# Switches.net
KiCad netlist of a schematic drawn in Altium Designer
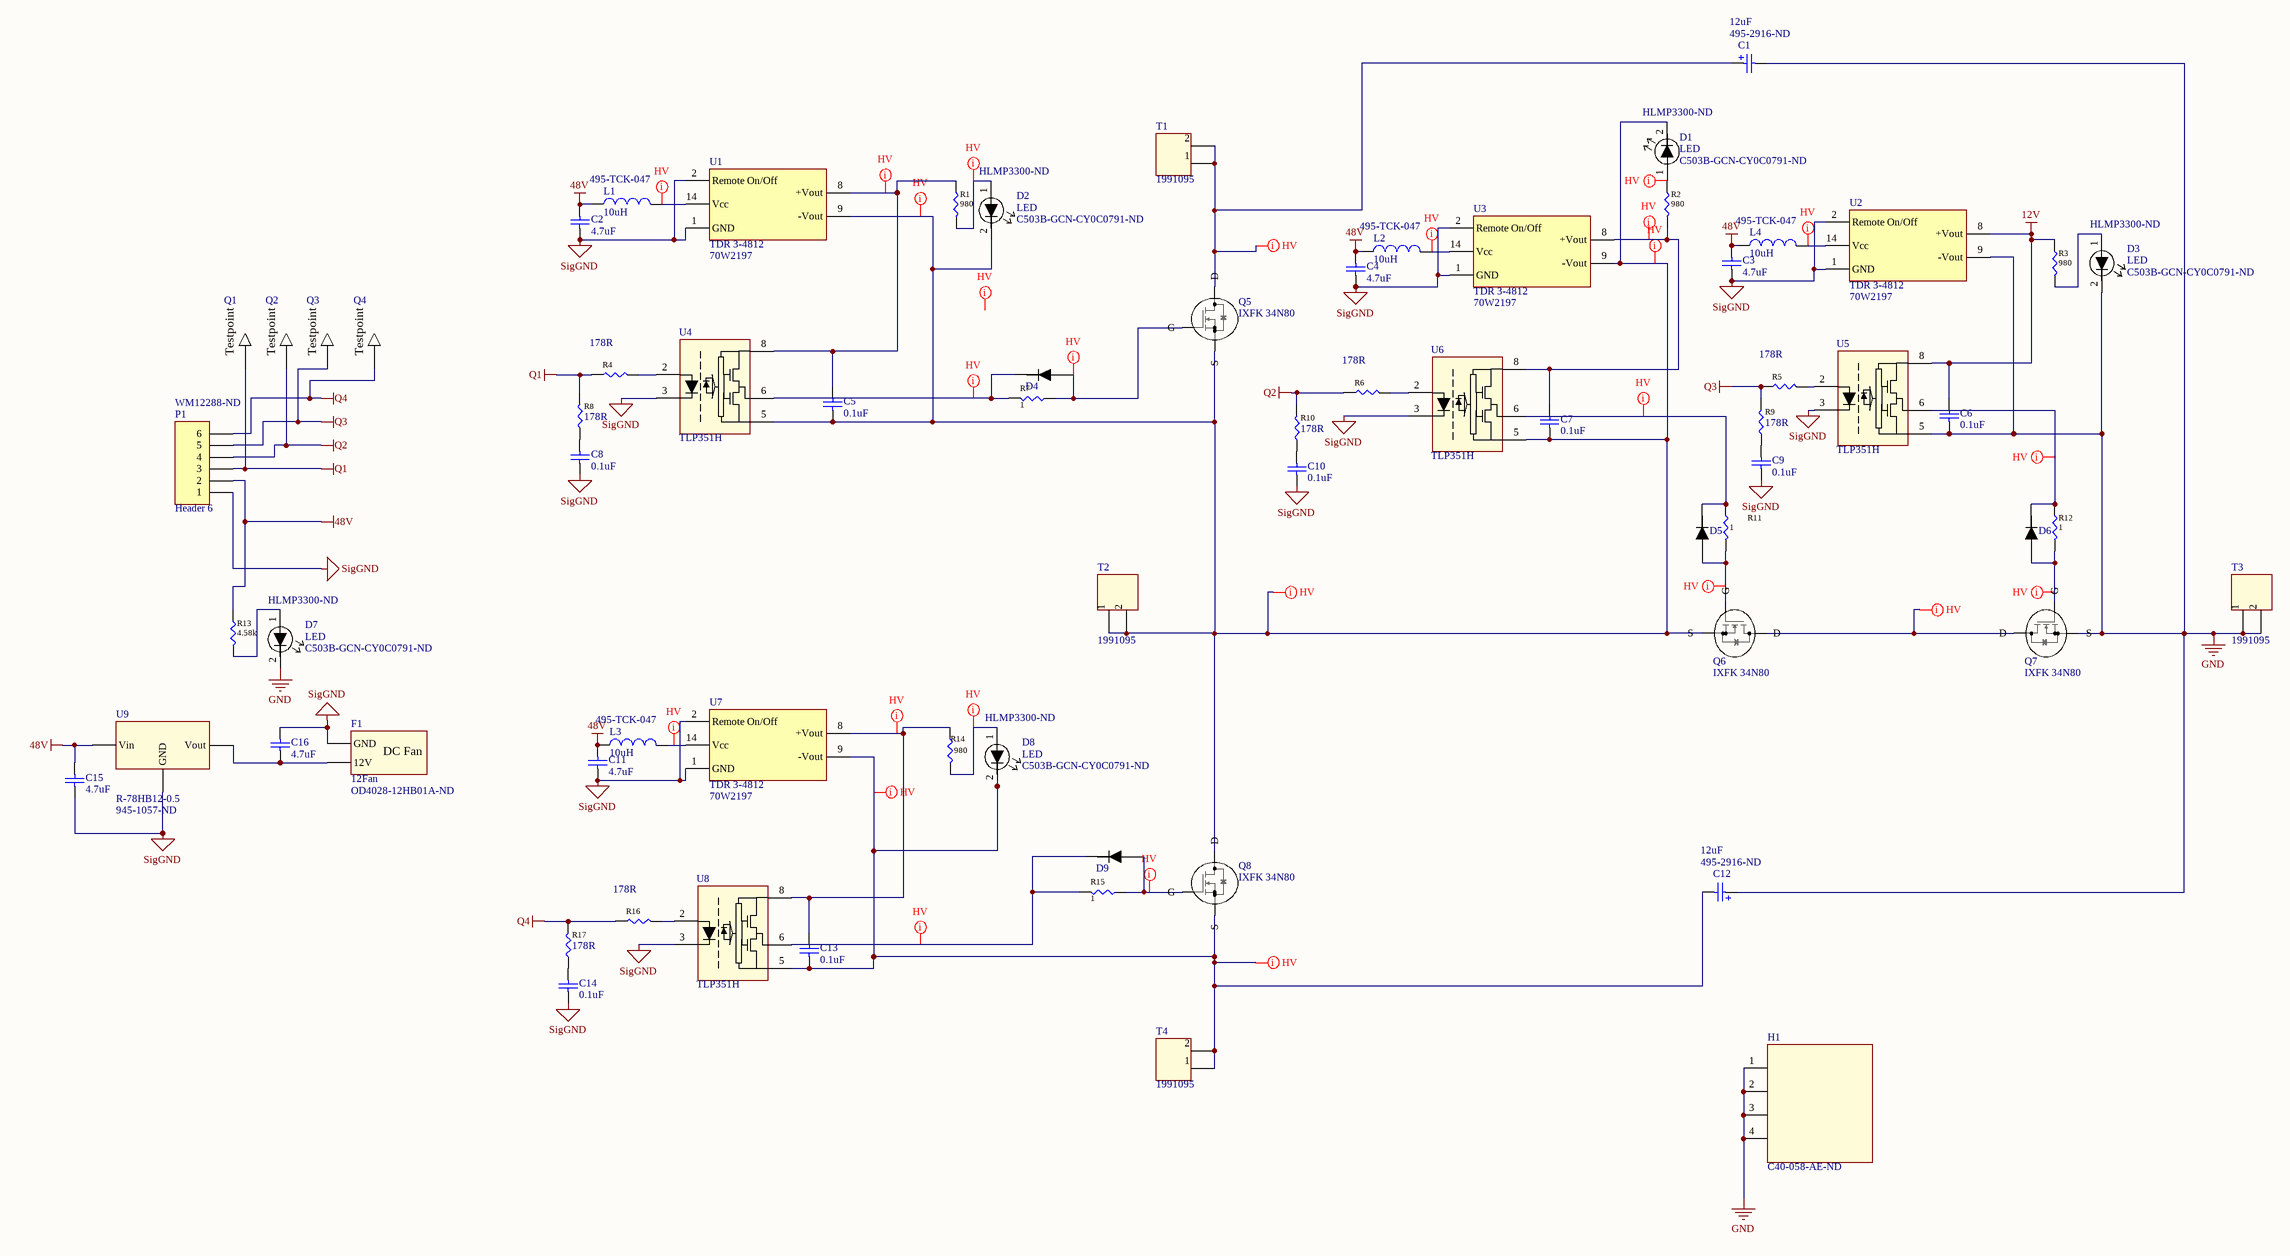
[diagram p0: Switches.SchDoc]

(export (version "E")
  (design (tool "Eeschema 10.0.6"))
  (components
    (comp (ref "C1")
      (value "Cap Pol1")
      (footprint "B32674D3126K000")
      (description "Polarized Capacitor (Radial)")
      (fields
        (field (name "SUPPLIER PART NUMBER 1") "495-2916-ND")
        (field (name "MANUFACTURER") "TDK EPCOS")
        (field (name "MANUFACTURER PART NUMBER") "B32674D3126K000")
        (field (name "CAPACITANCE") "12uF")
        (field (name "PUBLISHER") "Altium Limited")
      )
      (libsource (lib "T-Type Converter") (part "Cap Pol1"))
    )
    (comp (ref "C2")
      (value "4.7uF")
      (footprint "C4532")
      (description "Capacitor")
      (fields
        (field (name "MANUFACTURER") "TDK")
        (field (name "MANUFACTURER PART NUMBER") "CGA8N3X7S2A475K230KB")
        (field (name "PUBLISHER") "Altium Limited")
      )
      (libsource (lib "T-Type Converter") (part "Cap"))
    )
    (comp (ref "C3")
      (value "4.7uF")
      (footprint "C4532")
      (description "Capacitor")
      (fields
        (field (name "MANUFACTURER") "TDK")
        (field (name "MANUFACTURER PART NUMBER") "CGA8N3X7S2A475K230KB")
        (field (name "PUBLISHER") "Altium Limited")
      )
      (libsource (lib "T-Type Converter") (part "Cap"))
    )
    (comp (ref "C4")
      (value "4.7uF")
      (footprint "C4532")
      (description "Capacitor")
      (fields
        (field (name "MANUFACTURER") "TDK")
        (field (name "MANUFACTURER PART NUMBER") "CGA8N3X7S2A475K230KB")
        (field (name "PUBLISHER") "Altium Limited")
      )
      (libsource (lib "T-Type Converter") (part "Cap"))
    )
    (comp (ref "C5")
      (value "0.1uF")
      (footprint "R_1206")
      (description "Capacitor")
      (fields (field (name "Comment") "Cap") (field (name "PUBLISHER") "Altium Limited"))
      (libsource (lib "T-Type Converter") (part "Cap"))
    )
    (comp (ref "C6")
      (value "0.1uF")
      (footprint "R_1206")
      (description "Capacitor")
      (fields (field (name "Comment") "Cap") (field (name "PUBLISHER") "Altium Limited"))
      (libsource (lib "T-Type Converter") (part "Cap"))
    )
    (comp (ref "C7")
      (value "0.1uF")
      (footprint "R_1206")
      (description "Capacitor")
      (fields (field (name "Comment") "Cap") (field (name "PUBLISHER") "Altium Limited"))
      (libsource (lib "T-Type Converter") (part "Cap"))
    )
    (comp (ref "C8")
      (value "0.1uF")
      (footprint "Capacitor 0805 - duplicate")
      (description "Capacitor")
      (fields (field (name "Comment") "Cap") (field (name "PUBLISHER") "Altium Limited"))
      (libsource (lib "T-Type Converter") (part "Cap"))
    )
    (comp (ref "C9")
      (value "0.1uF")
      (footprint "Capacitor 0805 - duplicate")
      (description "Capacitor")
      (fields (field (name "Comment") "Cap") (field (name "PUBLISHER") "Altium Limited"))
      (libsource (lib "T-Type Converter") (part "Cap"))
    )
    (comp (ref "C10")
      (value "0.1uF")
      (footprint "Capacitor 0805 - duplicate")
      (description "Capacitor")
      (fields (field (name "Comment") "Cap") (field (name "PUBLISHER") "Altium Limited"))
      (libsource (lib "T-Type Converter") (part "Cap"))
    )
    (comp (ref "C11")
      (value "4.7uF")
      (footprint "C4532")
      (description "Capacitor")
      (fields
        (field (name "MANUFACTURER") "TDK")
        (field (name "MANUFACTURER PART NUMBER") "CGA8N3X7S2A475K230KB")
        (field (name "PUBLISHER") "Altium Limited")
      )
      (libsource (lib "T-Type Converter") (part "Cap"))
    )
    (comp (ref "C12")
      (value "Cap Pol1")
      (footprint "B32674D3126K000")
      (description "Polarized Capacitor (Radial)")
      (fields
        (field (name "SUPPLIER PART NUMBER 1") "495-2916-ND")
        (field (name "MANUFACTURER") "TDK EPCOS")
        (field (name "MANUFACTURER PART NUMBER") "B32674D3126K000")
        (field (name "CAPACITANCE") "12uF")
        (field (name "PUBLISHER") "Altium Limited")
      )
      (libsource (lib "T-Type Converter") (part "Cap Pol1"))
    )
    (comp (ref "C13")
      (value "0.1uF")
      (footprint "R_1206")
      (description "Capacitor")
      (fields (field (name "Comment") "Cap") (field (name "PUBLISHER") "Altium Limited"))
      (libsource (lib "T-Type Converter") (part "Cap"))
    )
    (comp (ref "C14")
      (value "0.1uF")
      (footprint "Capacitor 0805 - duplicate")
      (description "Capacitor")
      (fields (field (name "Comment") "Cap") (field (name "PUBLISHER") "Altium Limited"))
      (libsource (lib "T-Type Converter") (part "Cap"))
    )
    (comp (ref "C15")
      (value "4.7uF")
      (footprint "C4532")
      (description "Capacitor")
      (fields
        (field (name "MANUFACTURER") "TDK")
        (field (name "MANUFACTURER PART NUMBER") "CGA8N3X7S2A475K230KB")
        (field (name "PUBLISHER") "Altium Limited")
      )
      (libsource (lib "T-Type Converter") (part "Cap"))
    )
    (comp (ref "C16")
      (value "4.7uF")
      (footprint "C4532")
      (description "Capacitor")
      (fields
        (field (name "MANUFACTURER") "TDK")
        (field (name "MANUFACTURER PART NUMBER") "CGA8N3X7S2A475K230KB")
        (field (name "PUBLISHER") "Altium Limited")
      )
      (libsource (lib "T-Type Converter") (part "Cap"))
    )
    (comp (ref "D1")
      (value "LED")
      (footprint "LED")
      (fields
        (field (name "MANUFACTURER") "Cree")
        (field (name "MANUFACTURER PART NUMBER") "C503B-GCN-CY0C0791")
        (field (name "SUPPLIER PART NUMBER 1") "C503B-GCN-CY0C0791-ND")
        (field (name "SUPPLIER PART NUMBER 2") "HLMP3300-ND")
      )
      (libsource (lib "T-Type Converter") (part "LED"))
    )
    (comp (ref "D2")
      (value "LED")
      (footprint "LED")
      (fields
        (field (name "MANUFACTURER") "Cree")
        (field (name "MANUFACTURER PART NUMBER") "C503B-GCN-CY0C0791")
        (field (name "SUPPLIER PART NUMBER 1") "C503B-GCN-CY0C0791-ND")
        (field (name "SUPPLIER PART NUMBER 2") "HLMP3300-ND")
      )
      (libsource (lib "T-Type Converter") (part "LED"))
    )
    (comp (ref "D3")
      (value "LED")
      (footprint "LED")
      (fields
        (field (name "MANUFACTURER") "Cree")
        (field (name "MANUFACTURER PART NUMBER") "C503B-GCN-CY0C0791")
        (field (name "SUPPLIER PART NUMBER 1") "C503B-GCN-CY0C0791-ND")
        (field (name "SUPPLIER PART NUMBER 2") "HLMP3300-ND")
      )
      (libsource (lib "T-Type Converter") (part "LED"))
    )
    (comp (ref "D4")
      (value "1N4148")
      (footprint "DO-35_02")
      (description "Diode")
      (fields (field (name "MANUFACTURER") "Fairchild Semiconductor"))
      (libsource (lib "T-Type Converter") (part "1N4148"))
    )
    (comp (ref "D5")
      (value "1N4148")
      (footprint "DO-35_02")
      (description "Diode")
      (fields (field (name "MANUFACTURER") "Fairchild Semiconductor"))
      (libsource (lib "T-Type Converter") (part "1N4148"))
    )
    (comp (ref "D6")
      (value "1N4148")
      (footprint "DO-35_02")
      (description "Diode")
      (fields (field (name "MANUFACTURER") "Fairchild Semiconductor"))
      (libsource (lib "T-Type Converter") (part "1N4148"))
    )
    (comp (ref "D7")
      (value "LED")
      (footprint "LED")
      (fields
        (field (name "MANUFACTURER") "Cree")
        (field (name "MANUFACTURER PART NUMBER") "C503B-GCN-CY0C0791")
        (field (name "SUPPLIER PART NUMBER 1") "C503B-GCN-CY0C0791-ND")
        (field (name "SUPPLIER PART NUMBER 2") "HLMP3300-ND")
      )
      (libsource (lib "T-Type Converter") (part "LED"))
    )
    (comp (ref "D8")
      (value "LED")
      (footprint "LED")
      (fields
        (field (name "MANUFACTURER") "Cree")
        (field (name "MANUFACTURER PART NUMBER") "C503B-GCN-CY0C0791")
        (field (name "SUPPLIER PART NUMBER 1") "C503B-GCN-CY0C0791-ND")
        (field (name "SUPPLIER PART NUMBER 2") "HLMP3300-ND")
      )
      (libsource (lib "T-Type Converter") (part "LED"))
    )
    (comp (ref "D9")
      (value "1N4148")
      (footprint "DO-35_02")
      (description "Diode")
      (fields (field (name "MANUFACTURER") "Fairchild Semiconductor"))
      (libsource (lib "T-Type Converter") (part "1N4148"))
    )
    (comp (ref "F1")
      (value "12Fan")
      (footprint "12V Fan")
      (fields
        (field (name "MANUFACTURER") "Knight Electronics Orion")
        (field (name "MANUFACTURER PART NUMBER") "OD4028-12HB01A")
        (field (name "SUPPLIER PART NUMBER 1") "OD4028-12HB01A-ND")
      )
      (libsource (lib "T-Type Converter") (part "12Fan"))
    )
    (comp (ref "H1")
      (value "Heatsink")
      (footprint "Dual C40")
      (description "Dual C-40 Heatsink")
      (fields
        (field (name "MANUFACTURER") "Ohmite")
        (field (name "MANUFACTURER PART NUMBER") "C40-058-AE")
        (field (name "SUPPLIER PART NUMBER 1") "C40-058-AE-ND")
      )
      (libsource (lib "T-Type Converter") (part "C-40 Heatsink"))
    )
    (comp (ref "L1")
      (value "10uH")
      (footprint "TCK-047")
      (description "Inductor")
      (fields
        (field (name "SUPPLIER PART NUMBER 1") "495-TCK-047")
        (field (name "MANUFACTURER") "Traco Power")
        (field (name "MANUFACTURER PART NUMBER") "TCK-047")
        (field (name "PUBLISHER") "Altium Limited")
      )
      (libsource (lib "Miscellaneous Devices") (part "Inductor"))
    )
    (comp (ref "L2")
      (value "10uH")
      (footprint "TCK-047")
      (description "Inductor")
      (fields
        (field (name "SUPPLIER PART NUMBER 1") "495-TCK-047")
        (field (name "MANUFACTURER") "Traco Power")
        (field (name "MANUFACTURER PART NUMBER") "TCK-047")
        (field (name "PUBLISHER") "Altium Limited")
      )
      (libsource (lib "Miscellaneous Devices") (part "Inductor"))
    )
    (comp (ref "L3")
      (value "10uH")
      (footprint "TCK-047")
      (description "Inductor")
      (fields
        (field (name "SUPPLIER PART NUMBER 1") "495-TCK-047")
        (field (name "MANUFACTURER") "Traco Power")
        (field (name "MANUFACTURER PART NUMBER") "TCK-047")
        (field (name "PUBLISHER") "Altium Limited")
      )
      (libsource (lib "Miscellaneous Devices") (part "Inductor"))
    )
    (comp (ref "L4")
      (value "10uH")
      (footprint "TCK-047")
      (description "Inductor")
      (fields
        (field (name "SUPPLIER PART NUMBER 1") "495-TCK-047")
        (field (name "MANUFACTURER") "Traco Power")
        (field (name "MANUFACTURER PART NUMBER") "TCK-047")
        (field (name "PUBLISHER") "Altium Limited")
      )
      (libsource (lib "Miscellaneous Devices") (part "Inductor"))
    )
    (comp (ref "P1")
      (value "Header 6")
      (footprint "3.00mm Male Header")
      (description "Header, 6-Pin")
      (fields
        (field (name "SUPPLIER PART NUMBER 1") "WM12288-ND")
        (field (name "MANUFACTURER") "Molex")
        (field (name "MANUFACTURER PART NUMBER") "0559320610")
        (field (name "PUBLISHER") "Altium Limited")
      )
      (libsource (lib "Miscellaneous Connectors") (part "Header 6"))
    )
    (comp (ref "Q1")
      (value "Testpoint")
      (footprint "Testpoint")
      (libsource (lib "T-Type Converter") (part "Testpoint"))
    )
    (comp (ref "Q2")
      (value "Testpoint")
      (footprint "Testpoint")
      (libsource (lib "T-Type Converter") (part "Testpoint"))
    )
    (comp (ref "Q3")
      (value "Testpoint")
      (footprint "Testpoint")
      (libsource (lib "T-Type Converter") (part "Testpoint"))
    )
    (comp (ref "Q4")
      (value "Testpoint")
      (footprint "Testpoint")
      (libsource (lib "T-Type Converter") (part "Testpoint"))
    )
    (comp (ref "Q5")
      (value "IXFK 34N80")
      (footprint "TO-247")
      (description "MOSFET 34A")
      (fields (field (name "MANUFACTURER") "IXYS") (field (name "MANUFACTURER PART NUMBER") "IXFK34N80"))
      (libsource (lib "") (part "IXFK 34N80_2"))
    )
    (comp (ref "Q6")
      (value "IXFK 34N80")
      (footprint "TO-247")
      (description "MOSFET 34A")
      (fields (field (name "MANUFACTURER") "IXYS") (field (name "MANUFACTURER PART NUMBER") "IXFK34N80"))
      (libsource (lib "T-Type Converter") (part "IXFK 34N80"))
    )
    (comp (ref "Q7")
      (value "IXFK 34N80")
      (footprint "TO-247")
      (description "MOSFET 34A")
      (fields (field (name "MANUFACTURER") "IXYS") (field (name "MANUFACTURER PART NUMBER") "IXFK34N80"))
      (libsource (lib "") (part "IXFK 34N80_1"))
    )
    (comp (ref "Q8")
      (value "IXFK 34N80")
      (footprint "TO-247")
      (description "MOSFET 34A")
      (fields (field (name "MANUFACTURER") "IXYS") (field (name "MANUFACTURER PART NUMBER") "IXFK34N80"))
      (libsource (lib "") (part "IXFK 34N80_2"))
    )
    (comp (ref "R1")
      (value "980")
      (footprint "R_1206")
      (description "RES SMD 1% 1/4W 1206")
      (fields
        (field (name "MANUFACTURER") "Panasonic Electronic Components")
        (field (name "MANUFACTURER PART NUMBER") "ERJ-8ENF9101V")
      )
      (libsource (lib "T-Type Converter") (part "RES_SMD1"))
    )
    (comp (ref "R2")
      (value "980")
      (footprint "R_1206")
      (description "RES SMD 1% 1/4W 1206")
      (fields
        (field (name "MANUFACTURER") "Panasonic Electronic Components")
        (field (name "MANUFACTURER PART NUMBER") "ERJ-8ENF9101V")
      )
      (libsource (lib "T-Type Converter") (part "RES_SMD1"))
    )
    (comp (ref "R3")
      (value "980")
      (footprint "R_1206")
      (description "RES SMD 1% 1/4W 1206")
      (fields
        (field (name "MANUFACTURER") "Panasonic Electronic Components")
        (field (name "MANUFACTURER PART NUMBER") "ERJ-8ENF9101V")
      )
      (libsource (lib "T-Type Converter") (part "RES_SMD1"))
    )
    (comp (ref "R4")
      (value "~")
      (footprint "R_1206")
      (description "RES SMD 1% 1/4W 1206")
      (fields
        (field (name "MANUFACTURER") "Panasonic ECG")
        (field (name "MANUFACTURER PART NUMBER") "ERJ-8ENF1780V")
        (field (name "RESISTANCE") "178R")
      )
      (libsource (lib "T-Type Converter") (part "RES_SMD1"))
    )
    (comp (ref "R5")
      (value "~")
      (footprint "R_1206")
      (description "RES SMD 1% 1/4W 1206")
      (fields
        (field (name "MANUFACTURER") "Panasonic ECG")
        (field (name "MANUFACTURER PART NUMBER") "ERJ-8ENF1780V")
        (field (name "RESISTANCE") "178R")
      )
      (libsource (lib "T-Type Converter") (part "RES_SMD1"))
    )
    (comp (ref "R6")
      (value "~")
      (footprint "R_1206")
      (description "RES SMD 1% 1/4W 1206")
      (fields
        (field (name "MANUFACTURER") "Panasonic ECG")
        (field (name "MANUFACTURER PART NUMBER") "ERJ-8ENF1780V")
        (field (name "RESISTANCE") "178R")
      )
      (libsource (lib "T-Type Converter") (part "RES_SMD1"))
    )
    (comp (ref "R7")
      (value "1")
      (footprint "R_1206")
      (description "RES SMD 1% 1/4W 1206")
      (fields
        (field (name "MANUFACTURER") "Panasonic Electronic Components")
        (field (name "MANUFACTURER PART NUMBER") "ERJ-8ENF9101V")
      )
      (libsource (lib "T-Type Converter") (part "RES_SMD1"))
    )
    (comp (ref "R8")
      (value "~")
      (footprint "R_1206")
      (description "RES SMD 1% 1/4W 1206")
      (fields
        (field (name "MANUFACTURER") "Panasonic ECG")
        (field (name "MANUFACTURER PART NUMBER") "ERJ-8ENF1780V")
        (field (name "RESISTANCE") "178R")
      )
      (libsource (lib "T-Type Converter") (part "RES_SMD1"))
    )
    (comp (ref "R9")
      (value "~")
      (footprint "R_1206")
      (description "RES SMD 1% 1/4W 1206")
      (fields
        (field (name "MANUFACTURER") "Panasonic ECG")
        (field (name "MANUFACTURER PART NUMBER") "ERJ-8ENF1780V")
        (field (name "RESISTANCE") "178R")
      )
      (libsource (lib "T-Type Converter") (part "RES_SMD1"))
    )
    (comp (ref "R10")
      (value "~")
      (footprint "R_1206")
      (description "RES SMD 1% 1/4W 1206")
      (fields
        (field (name "MANUFACTURER") "Panasonic ECG")
        (field (name "MANUFACTURER PART NUMBER") "ERJ-8ENF1780V")
        (field (name "RESISTANCE") "178R")
      )
      (libsource (lib "T-Type Converter") (part "RES_SMD1"))
    )
    (comp (ref "R11")
      (value "1")
      (footprint "R_1206")
      (description "RES SMD 1% 1/4W 1206")
      (fields
        (field (name "MANUFACTURER") "Panasonic Electronic Components")
        (field (name "MANUFACTURER PART NUMBER") "ERJ-8ENF9101V")
      )
      (libsource (lib "T-Type Converter") (part "RES_SMD1"))
    )
    (comp (ref "R12")
      (value "1")
      (footprint "R_1206")
      (description "RES SMD 1% 1/4W 1206")
      (fields
        (field (name "MANUFACTURER") "Panasonic Electronic Components")
        (field (name "MANUFACTURER PART NUMBER") "ERJ-8ENF9101V")
      )
      (libsource (lib "T-Type Converter") (part "RES_SMD1"))
    )
    (comp (ref "R13")
      (value "4.58k")
      (footprint "R_1206")
      (description "RES SMD 1% 1/4W 1206")
      (fields
        (field (name "MANUFACTURER") "Panasonic Electronic Components")
        (field (name "MANUFACTURER PART NUMBER") "ERJ-8ENF9101V")
      )
      (libsource (lib "T-Type Converter") (part "RES_SMD1"))
    )
    (comp (ref "R14")
      (value "980")
      (footprint "R_1206")
      (description "RES SMD 1% 1/4W 1206")
      (fields
        (field (name "MANUFACTURER") "Panasonic Electronic Components")
        (field (name "MANUFACTURER PART NUMBER") "ERJ-8ENF9101V")
      )
      (libsource (lib "T-Type Converter") (part "RES_SMD1"))
    )
    (comp (ref "R15")
      (value "1")
      (footprint "R_1206")
      (description "RES SMD 1% 1/4W 1206")
      (fields
        (field (name "MANUFACTURER") "Panasonic Electronic Components")
        (field (name "MANUFACTURER PART NUMBER") "ERJ-8ENF9101V")
      )
      (libsource (lib "T-Type Converter") (part "RES_SMD1"))
    )
    (comp (ref "R16")
      (value "~")
      (footprint "R_1206")
      (description "RES SMD 1% 1/4W 1206")
      (fields
        (field (name "MANUFACTURER") "Panasonic ECG")
        (field (name "MANUFACTURER PART NUMBER") "ERJ-8ENF1780V")
        (field (name "RESISTANCE") "178R")
      )
      (libsource (lib "T-Type Converter") (part "RES_SMD1"))
    )
    (comp (ref "R17")
      (value "~")
      (footprint "R_1206")
      (description "RES SMD 1% 1/4W 1206")
      (fields
        (field (name "MANUFACTURER") "Panasonic ECG")
        (field (name "MANUFACTURER PART NUMBER") "ERJ-8ENF1780V")
        (field (name "RESISTANCE") "178R")
      )
      (libsource (lib "T-Type Converter") (part "RES_SMD1"))
    )
    (comp (ref "T1")
      (value "1991095")
      (footprint "Terminal Pad")
      (description "2 way terminal block")
      (fields (field (name "MANUFACTURER") "Phoenix Contact") (field (name "VOLTAGE") "300V"))
      (libsource (lib "") (part "Terminal Block 2_1"))
    )
    (comp (ref "T2")
      (value "1991095")
      (footprint "Terminal Pad")
      (description "2 way terminal block")
      (fields (field (name "MANUFACTURER") "Phoenix Contact") (field (name "VOLTAGE") "300V"))
      (libsource (lib "T-Type Converter") (part "Terminal Block 2"))
    )
    (comp (ref "T3")
      (value "1991095")
      (footprint "Terminal Pad")
      (description "2 way terminal block")
      (fields (field (name "MANUFACTURER") "Phoenix Contact") (field (name "VOLTAGE") "300V"))
      (libsource (lib "T-Type Converter") (part "Terminal Block 2"))
    )
    (comp (ref "T4")
      (value "1991095")
      (footprint "Terminal Pad")
      (description "2 way terminal block")
      (fields (field (name "MANUFACTURER") "Phoenix Contact") (field (name "VOLTAGE") "300V"))
      (libsource (lib "") (part "Terminal Block 2_1"))
    )
    (comp (ref "U1")
      (value "TDR 3-4812")
      (footprint "PID DC-DC Converter - duplicate")
      (description "48V-12V Converter")
      (fields
        (field (name "MANUFACTURER") "Traco Power")
        (field (name "MANUFACTURER PART NUMBER") "TDR3-4812WI")
        (field (name "SUPPLIER PART NUMBER 1") "70W2197")
      )
      (libsource (lib "T-Type Converter") (part "TDR 3-4812"))
    )
    (comp (ref "U2")
      (value "TDR 3-4812")
      (footprint "PID DC-DC Converter - duplicate")
      (description "48V-12V Converter")
      (fields
        (field (name "MANUFACTURER") "Traco Power")
        (field (name "MANUFACTURER PART NUMBER") "TDR3-4812WI")
        (field (name "SUPPLIER PART NUMBER 1") "70W2197")
      )
      (libsource (lib "T-Type Converter") (part "TDR 3-4812"))
    )
    (comp (ref "U3")
      (value "TDR 3-4812")
      (footprint "PID DC-DC Converter - duplicate")
      (description "48V-12V Converter")
      (fields
        (field (name "MANUFACTURER") "Traco Power")
        (field (name "MANUFACTURER PART NUMBER") "TDR3-4812WI")
        (field (name "SUPPLIER PART NUMBER 1") "70W2197")
      )
      (libsource (lib "T-Type Converter") (part "TDR 3-4812"))
    )
    (comp (ref "U4")
      (value "TLP351H")
      (footprint "11-10C4S")
      (description "Photocoupler Driver")
      (fields (field (name "MANUFACTURER") "Toshiba"))
      (libsource (lib "T-Type Converter") (part "TLP351H"))
    )
    (comp (ref "U5")
      (value "TLP351H")
      (footprint "11-10C4S")
      (description "Photocoupler Driver")
      (fields (field (name "MANUFACTURER") "Toshiba"))
      (libsource (lib "T-Type Converter") (part "TLP351H"))
    )
    (comp (ref "U6")
      (value "TLP351H")
      (footprint "11-10C4S")
      (description "Photocoupler Driver")
      (fields (field (name "MANUFACTURER") "Toshiba"))
      (libsource (lib "T-Type Converter") (part "TLP351H"))
    )
    (comp (ref "U7")
      (value "TDR 3-4812")
      (footprint "PID DC-DC Converter - duplicate")
      (description "48V-12V Converter")
      (fields
        (field (name "MANUFACTURER") "Traco Power")
        (field (name "MANUFACTURER PART NUMBER") "TDR3-4812WI")
        (field (name "SUPPLIER PART NUMBER 1") "70W2197")
      )
      (libsource (lib "T-Type Converter") (part "TDR 3-4812"))
    )
    (comp (ref "U8")
      (value "TLP351H")
      (footprint "11-10C4S")
      (description "Photocoupler Driver")
      (fields (field (name "MANUFACTURER") "Toshiba"))
      (libsource (lib "T-Type Converter") (part "TLP351H"))
    )
    (comp (ref "U9")
      (value "R-78HB12-0.5")
      (footprint "R-78HB12-0.5 Footprint")
      (fields (field (name "MANUFACTURER") "Recom") (field (name "SUPPLIER PART NUMBER 1") "945-1057-ND"))
      (libsource (lib "T-Type Converter") (part "R-78HB12-0.5"))
    )
  )
  (nets
    (net (code "1") (name "12V") (class "Default")
      (node (ref "C6") (pin "2") (pinfunction "2_2") (pintype "passive"))
      (node (ref "R3") (pin "2") (pinfunction "2_2") (pintype "passive"))
      (node (ref "U2") (pin "8") (pinfunction "+Vout_8") (pintype "passive"))
      (node (ref "U5") (pin "8") (pinfunction "8_8") (pintype "power_in"))
    )
    (net (code "2") (name "48V") (class "Default")
      (node (ref "C11") (pin "2") (pinfunction "2_2") (pintype "passive"))
      (node (ref "C15") (pin "2") (pinfunction "2_2") (pintype "passive"))
      (node (ref "C2") (pin "2") (pinfunction "2_2") (pintype "passive"))
      (node (ref "C3") (pin "2") (pinfunction "2_2") (pintype "passive"))
      (node (ref "C4") (pin "2") (pinfunction "2_2") (pintype "passive"))
      (node (ref "L1") (pin "1") (pinfunction "1_1") (pintype "passive"))
      (node (ref "L2") (pin "1") (pinfunction "1_1") (pintype "passive"))
      (node (ref "L3") (pin "1") (pinfunction "1_1") (pintype "passive"))
      (node (ref "L4") (pin "1") (pinfunction "1_1") (pintype "passive"))
      (node (ref "P1") (pin "2") (pinfunction "2_2") (pintype "passive"))
      (node (ref "R13") (pin "2") (pinfunction "2_2") (pintype "passive"))
      (node (ref "U9") (pin "1") (pinfunction "Vin_1") (pintype "power_in"))
    )
    (net (code "3") (name "GND") (class "Default")
      (node (ref "C1") (pin "2") (pinfunction "2_2") (pintype "passive"))
      (node (ref "C12") (pin "1") (pinfunction "1_1") (pintype "passive"))
      (node (ref "C6") (pin "1") (pinfunction "1_1") (pintype "passive"))
      (node (ref "D3") (pin "2") (pinfunction "Cathode_2") (pintype "passive"))
      (node (ref "D7") (pin "2") (pinfunction "Cathode_2") (pintype "passive"))
      (node (ref "H1") (pin "1") (pinfunction "1_1") (pintype "power_in"))
      (node (ref "H1") (pin "2") (pinfunction "2_2") (pintype "power_in"))
      (node (ref "H1") (pin "3") (pinfunction "3_3") (pintype "power_in"))
      (node (ref "H1") (pin "4") (pinfunction "4_4") (pintype "power_in"))
      (node (ref "Q7") (pin "3") (pinfunction "S_3") (pintype "passive"))
      (node (ref "T3") (pin "1") (pintype "power_in"))
      (node (ref "T3") (pin "2") (pintype "power_in"))
      (node (ref "U2") (pin "9") (pinfunction "-Vout_9") (pintype "passive"))
      (node (ref "U5") (pin "5") (pinfunction "5_5") (pintype "power_in"))
    )
    (net (code "4") (name "Net-(C8-Pad2)") (class "Default")
      (node (ref "C8") (pin "2") (pinfunction "2_2") (pintype "passive"))
      (node (ref "R8") (pin "2") (pinfunction "2_2") (pintype "passive"))
    )
    (net (code "5") (name "Net-(C9-Pad2)") (class "Default")
      (node (ref "C9") (pin "2") (pinfunction "2_2") (pintype "passive"))
      (node (ref "R9") (pin "2") (pinfunction "2_2") (pintype "passive"))
    )
    (net (code "6") (name "Net-(C10-Pad2)") (class "Default")
      (node (ref "C10") (pin "2") (pinfunction "2_2") (pintype "passive"))
      (node (ref "R10") (pin "2") (pinfunction "2_2") (pintype "passive"))
    )
    (net (code "7") (name "Net-(C14-Pad2)") (class "Default")
      (node (ref "C14") (pin "2") (pinfunction "2_2") (pintype "passive"))
      (node (ref "R17") (pin "2") (pinfunction "2_2") (pintype "passive"))
    )
    (net (code "8") (name "Net-(D1-Anode)") (class "Default")
      (node (ref "D1") (pin "1") (pinfunction "Anode_1") (pintype "passive"))
      (node (ref "R2") (pin "2") (pinfunction "2_2") (pintype "passive"))
    )
    (net (code "9") (name "Net-(D1-Cathode)") (class "Default")
      (node (ref "C5") (pin "1") (pinfunction "1_1") (pintype "passive"))
      (node (ref "C7") (pin "1") (pinfunction "1_1") (pintype "passive"))
      (node (ref "D1") (pin "2") (pinfunction "Cathode_2") (pintype "passive"))
      (node (ref "D2") (pin "2") (pinfunction "Cathode_2") (pintype "passive"))
      (node (ref "Q5") (pin "3") (pinfunction "S_3") (pintype "passive"))
      (node (ref "Q6") (pin "3") (pinfunction "S_3") (pintype "passive"))
      (node (ref "Q8") (pin "2") (pinfunction "D_2") (pintype "passive"))
      (node (ref "T2") (pin "1") (pintype "power_in"))
      (node (ref "T2") (pin "2") (pintype "power_in"))
      (node (ref "U1") (pin "9") (pinfunction "-Vout_9") (pintype "passive"))
      (node (ref "U3") (pin "9") (pinfunction "-Vout_9") (pintype "passive"))
      (node (ref "U4") (pin "5") (pinfunction "5_5") (pintype "power_in"))
      (node (ref "U6") (pin "5") (pinfunction "5_5") (pintype "power_in"))
    )
    (net (code "10") (name "Net-(D2-Anode)") (class "Default")
      (node (ref "D2") (pin "1") (pinfunction "Anode_1") (pintype "passive"))
      (node (ref "R1") (pin "1") (pinfunction "1_1") (pintype "passive"))
    )
    (net (code "11") (name "Net-(D3-Anode)") (class "Default")
      (node (ref "D3") (pin "1") (pinfunction "Anode_1") (pintype "passive"))
      (node (ref "R3") (pin "1") (pinfunction "1_1") (pintype "passive"))
    )
    (net (code "12") (name "Net-(D4-Anode)") (class "Default")
      (node (ref "D4") (pin "2") (pinfunction "Anode_2") (pintype "passive"))
      (node (ref "Q5") (pin "1") (pinfunction "G_1") (pintype "passive"))
      (node (ref "R7") (pin "2") (pinfunction "2_2") (pintype "passive"))
    )
    (net (code "13") (name "Net-(D4-Cathode)") (class "Default")
      (node (ref "D4") (pin "1") (pinfunction "Cathode_1") (pintype "passive"))
      (node (ref "R7") (pin "1") (pinfunction "1_1") (pintype "passive"))
      (node (ref "U4") (pin "6") (pinfunction "6_6") (pintype "power_in"))
    )
    (net (code "14") (name "Net-(D5-Anode)") (class "Default")
      (node (ref "D5") (pin "2") (pinfunction "Anode_2") (pintype "passive"))
      (node (ref "Q6") (pin "1") (pinfunction "G_1") (pintype "passive"))
      (node (ref "R11") (pin "1") (pinfunction "1_1") (pintype "passive"))
    )
    (net (code "15") (name "Net-(D5-Cathode)") (class "Default")
      (node (ref "D5") (pin "1") (pinfunction "Cathode_1") (pintype "passive"))
      (node (ref "R11") (pin "2") (pinfunction "2_2") (pintype "passive"))
      (node (ref "U6") (pin "6") (pinfunction "6_6") (pintype "power_in"))
    )
    (net (code "16") (name "Net-(D6-Anode)") (class "Default")
      (node (ref "D6") (pin "2") (pinfunction "Anode_2") (pintype "passive"))
      (node (ref "Q7") (pin "1") (pinfunction "G_1") (pintype "passive"))
      (node (ref "R12") (pin "1") (pinfunction "1_1") (pintype "passive"))
    )
    (net (code "17") (name "Net-(D6-Cathode)") (class "Default")
      (node (ref "D6") (pin "1") (pinfunction "Cathode_1") (pintype "passive"))
      (node (ref "R12") (pin "2") (pinfunction "2_2") (pintype "passive"))
      (node (ref "U5") (pin "6") (pinfunction "6_6") (pintype "power_in"))
    )
    (net (code "18") (name "Net-(D7-Anode)") (class "Default")
      (node (ref "D7") (pin "1") (pinfunction "Anode_1") (pintype "passive"))
      (node (ref "R13") (pin "1") (pinfunction "1_1") (pintype "passive"))
    )
    (net (code "19") (name "Net-(D8-Anode)") (class "Default")
      (node (ref "D8") (pin "1") (pinfunction "Anode_1") (pintype "passive"))
      (node (ref "R14") (pin "1") (pinfunction "1_1") (pintype "passive"))
    )
    (net (code "20") (name "Net-(D8-Cathode)") (class "Default")
      (node (ref "C12") (pin "2") (pinfunction "2_2") (pintype "passive"))
      (node (ref "C13") (pin "1") (pinfunction "1_1") (pintype "passive"))
      (node (ref "D8") (pin "2") (pinfunction "Cathode_2") (pintype "passive"))
      (node (ref "Q8") (pin "3") (pinfunction "S_3") (pintype "passive"))
      (node (ref "T4") (pin "1") (pintype "power_in"))
      (node (ref "T4") (pin "2") (pintype "power_in"))
      (node (ref "U7") (pin "9") (pinfunction "-Vout_9") (pintype "passive"))
      (node (ref "U8") (pin "5") (pinfunction "5_5") (pintype "power_in"))
    )
    (net (code "21") (name "Net-(D9-Anode)") (class "Default")
      (node (ref "D9") (pin "2") (pinfunction "Anode_2") (pintype "passive"))
      (node (ref "Q8") (pin "1") (pinfunction "G_1") (pintype "passive"))
      (node (ref "R15") (pin "2") (pinfunction "2_2") (pintype "passive"))
    )
    (net (code "22") (name "Net-(D9-Cathode)") (class "Default")
      (node (ref "D9") (pin "1") (pinfunction "Cathode_1") (pintype "passive"))
      (node (ref "R15") (pin "1") (pinfunction "1_1") (pintype "passive"))
      (node (ref "U8") (pin "6") (pinfunction "6_6") (pintype "power_in"))
    )
    (net (code "23") (name "Net-(F1-12V)") (class "Default")
      (node (ref "C16") (pin "1") (pinfunction "1_1") (pintype "passive"))
      (node (ref "F1") (pin "1") (pinfunction "12V_1") (pintype "power_in"))
      (node (ref "U9") (pin "3") (pinfunction "Vout_3") (pintype "power_in"))
    )
    (net (code "24") (name "Net-(Q5-D)") (class "Default")
      (node (ref "C1") (pin "1") (pinfunction "1_1") (pintype "passive"))
      (node (ref "Q5") (pin "2") (pinfunction "D_2") (pintype "passive"))
      (node (ref "T1") (pin "1") (pintype "power_in"))
      (node (ref "T1") (pin "2") (pintype "power_in"))
    )
    (net (code "25") (name "Net-(Q6-D)") (class "Default")
      (node (ref "Q6") (pin "2") (pinfunction "D_2") (pintype "passive"))
      (node (ref "Q7") (pin "2") (pinfunction "D_2") (pintype "passive"))
    )
    (net (code "26") (name "Net-(R4-Pad1)") (class "Default")
      (node (ref "R4") (pin "1") (pinfunction "1_1") (pintype "passive"))
      (node (ref "U4") (pin "2") (pinfunction "2_2") (pintype "power_in"))
    )
    (net (code "27") (name "Net-(R5-Pad1)") (class "Default")
      (node (ref "R5") (pin "1") (pinfunction "1_1") (pintype "passive"))
      (node (ref "U5") (pin "2") (pinfunction "2_2") (pintype "power_in"))
    )
    (net (code "28") (name "Net-(R6-Pad1)") (class "Default")
      (node (ref "R6") (pin "1") (pinfunction "1_1") (pintype "passive"))
      (node (ref "U6") (pin "2") (pinfunction "2_2") (pintype "power_in"))
    )
    (net (code "29") (name "Net-(R16-Pad1)") (class "Default")
      (node (ref "R16") (pin "1") (pinfunction "1_1") (pintype "passive"))
      (node (ref "U8") (pin "2") (pinfunction "2_2") (pintype "power_in"))
    )
    (net (code "30") (name "Net-(U1-+Vout)") (class "Default")
      (node (ref "C5") (pin "2") (pinfunction "2_2") (pintype "passive"))
      (node (ref "R1") (pin "2") (pinfunction "2_2") (pintype "passive"))
      (node (ref "U1") (pin "8") (pinfunction "+Vout_8") (pintype "passive"))
      (node (ref "U4") (pin "8") (pinfunction "8_8") (pintype "power_in"))
    )
    (net (code "31") (name "Net-(U1-Vcc)") (class "Default")
      (node (ref "L1") (pin "2") (pinfunction "2_2") (pintype "passive"))
      (node (ref "U1") (pin "14") (pinfunction "Vcc_14") (pintype "passive"))
    )
    (net (code "32") (name "Net-(U2-Vcc)") (class "Default")
      (node (ref "L4") (pin "2") (pinfunction "2_2") (pintype "passive"))
      (node (ref "U2") (pin "14") (pinfunction "Vcc_14") (pintype "passive"))
    )
    (net (code "33") (name "Net-(U3-+Vout)") (class "Default")
      (node (ref "C7") (pin "2") (pinfunction "2_2") (pintype "passive"))
      (node (ref "R2") (pin "1") (pinfunction "1_1") (pintype "passive"))
      (node (ref "U3") (pin "8") (pinfunction "+Vout_8") (pintype "passive"))
      (node (ref "U6") (pin "8") (pinfunction "8_8") (pintype "power_in"))
    )
    (net (code "34") (name "Net-(U3-Vcc)") (class "Default")
      (node (ref "L2") (pin "2") (pinfunction "2_2") (pintype "passive"))
      (node (ref "U3") (pin "14") (pinfunction "Vcc_14") (pintype "passive"))
    )
    (net (code "35") (name "Net-(U7-+Vout)") (class "Default")
      (node (ref "C13") (pin "2") (pinfunction "2_2") (pintype "passive"))
      (node (ref "R14") (pin "2") (pinfunction "2_2") (pintype "passive"))
      (node (ref "U7") (pin "8") (pinfunction "+Vout_8") (pintype "passive"))
      (node (ref "U8") (pin "8") (pinfunction "8_8") (pintype "power_in"))
    )
    (net (code "36") (name "Net-(U7-Vcc)") (class "Default")
      (node (ref "L3") (pin "2") (pinfunction "2_2") (pintype "passive"))
      (node (ref "U7") (pin "14") (pinfunction "Vcc_14") (pintype "passive"))
    )
    (net (code "37") (name "Q1") (class "Default")
      (node (ref "P1") (pin "3") (pinfunction "3_3") (pintype "passive"))
      (node (ref "Q1") (pin "1") (pinfunction "1_1") (pintype "power_in"))
      (node (ref "R4") (pin "2") (pinfunction "2_2") (pintype "passive"))
      (node (ref "R8") (pin "1") (pinfunction "1_1") (pintype "passive"))
    )
    (net (code "38") (name "Q2") (class "Default")
      (node (ref "P1") (pin "4") (pinfunction "4_4") (pintype "passive"))
      (node (ref "Q2") (pin "1") (pinfunction "1_1") (pintype "power_in"))
      (node (ref "R10") (pin "1") (pinfunction "1_1") (pintype "passive"))
      (node (ref "R6") (pin "2") (pinfunction "2_2") (pintype "passive"))
    )
    (net (code "39") (name "Q3") (class "Default")
      (node (ref "P1") (pin "5") (pinfunction "5_5") (pintype "passive"))
      (node (ref "Q3") (pin "1") (pinfunction "1_1") (pintype "power_in"))
      (node (ref "R5") (pin "2") (pinfunction "2_2") (pintype "passive"))
      (node (ref "R9") (pin "1") (pinfunction "1_1") (pintype "passive"))
    )
    (net (code "40") (name "Q4") (class "Default")
      (node (ref "P1") (pin "6") (pinfunction "6_6") (pintype "passive"))
      (node (ref "Q4") (pin "1") (pinfunction "1_1") (pintype "power_in"))
      (node (ref "R16") (pin "2") (pinfunction "2_2") (pintype "passive"))
      (node (ref "R17") (pin "1") (pinfunction "1_1") (pintype "passive"))
    )
    (net (code "41") (name "SigGND") (class "Default")
      (node (ref "C10") (pin "1") (pinfunction "1_1") (pintype "passive"))
      (node (ref "C11") (pin "1") (pinfunction "1_1") (pintype "passive"))
      (node (ref "C14") (pin "1") (pinfunction "1_1") (pintype "passive"))
      (node (ref "C15") (pin "1") (pinfunction "1_1") (pintype "passive"))
      (node (ref "C16") (pin "2") (pinfunction "2_2") (pintype "passive"))
      (node (ref "C2") (pin "1") (pinfunction "1_1") (pintype "passive"))
      (node (ref "C3") (pin "1") (pinfunction "1_1") (pintype "passive"))
      (node (ref "C4") (pin "1") (pinfunction "1_1") (pintype "passive"))
      (node (ref "C8") (pin "1") (pinfunction "1_1") (pintype "passive"))
      (node (ref "C9") (pin "1") (pinfunction "1_1") (pintype "passive"))
      (node (ref "F1") (pin "2") (pinfunction "GND_2") (pintype "power_in"))
      (node (ref "P1") (pin "1") (pinfunction "1_1") (pintype "passive"))
      (node (ref "U1") (pin "1") (pinfunction "GND_1") (pintype "power_in"))
      (node (ref "U1") (pin "2") (pinfunction "Remote_On/Off_2") (pintype "passive"))
      (node (ref "U2") (pin "1") (pinfunction "GND_1") (pintype "power_in"))
      (node (ref "U2") (pin "2") (pinfunction "Remote_On/Off_2") (pintype "passive"))
      (node (ref "U3") (pin "1") (pinfunction "GND_1") (pintype "power_in"))
      (node (ref "U3") (pin "2") (pinfunction "Remote_On/Off_2") (pintype "passive"))
      (node (ref "U4") (pin "3") (pinfunction "3_3") (pintype "power_in"))
      (node (ref "U5") (pin "3") (pinfunction "3_3") (pintype "power_in"))
      (node (ref "U6") (pin "3") (pinfunction "3_3") (pintype "power_in"))
      (node (ref "U7") (pin "1") (pinfunction "GND_1") (pintype "power_in"))
      (node (ref "U7") (pin "2") (pinfunction "Remote_On/Off_2") (pintype "passive"))
      (node (ref "U8") (pin "3") (pinfunction "3_3") (pintype "power_in"))
      (node (ref "U9") (pin "2") (pinfunction "GND_2") (pintype "power_in"))
    )
  )
)
